# schematics.net
KiCad netlist of a schematic drawn in EasyEDA
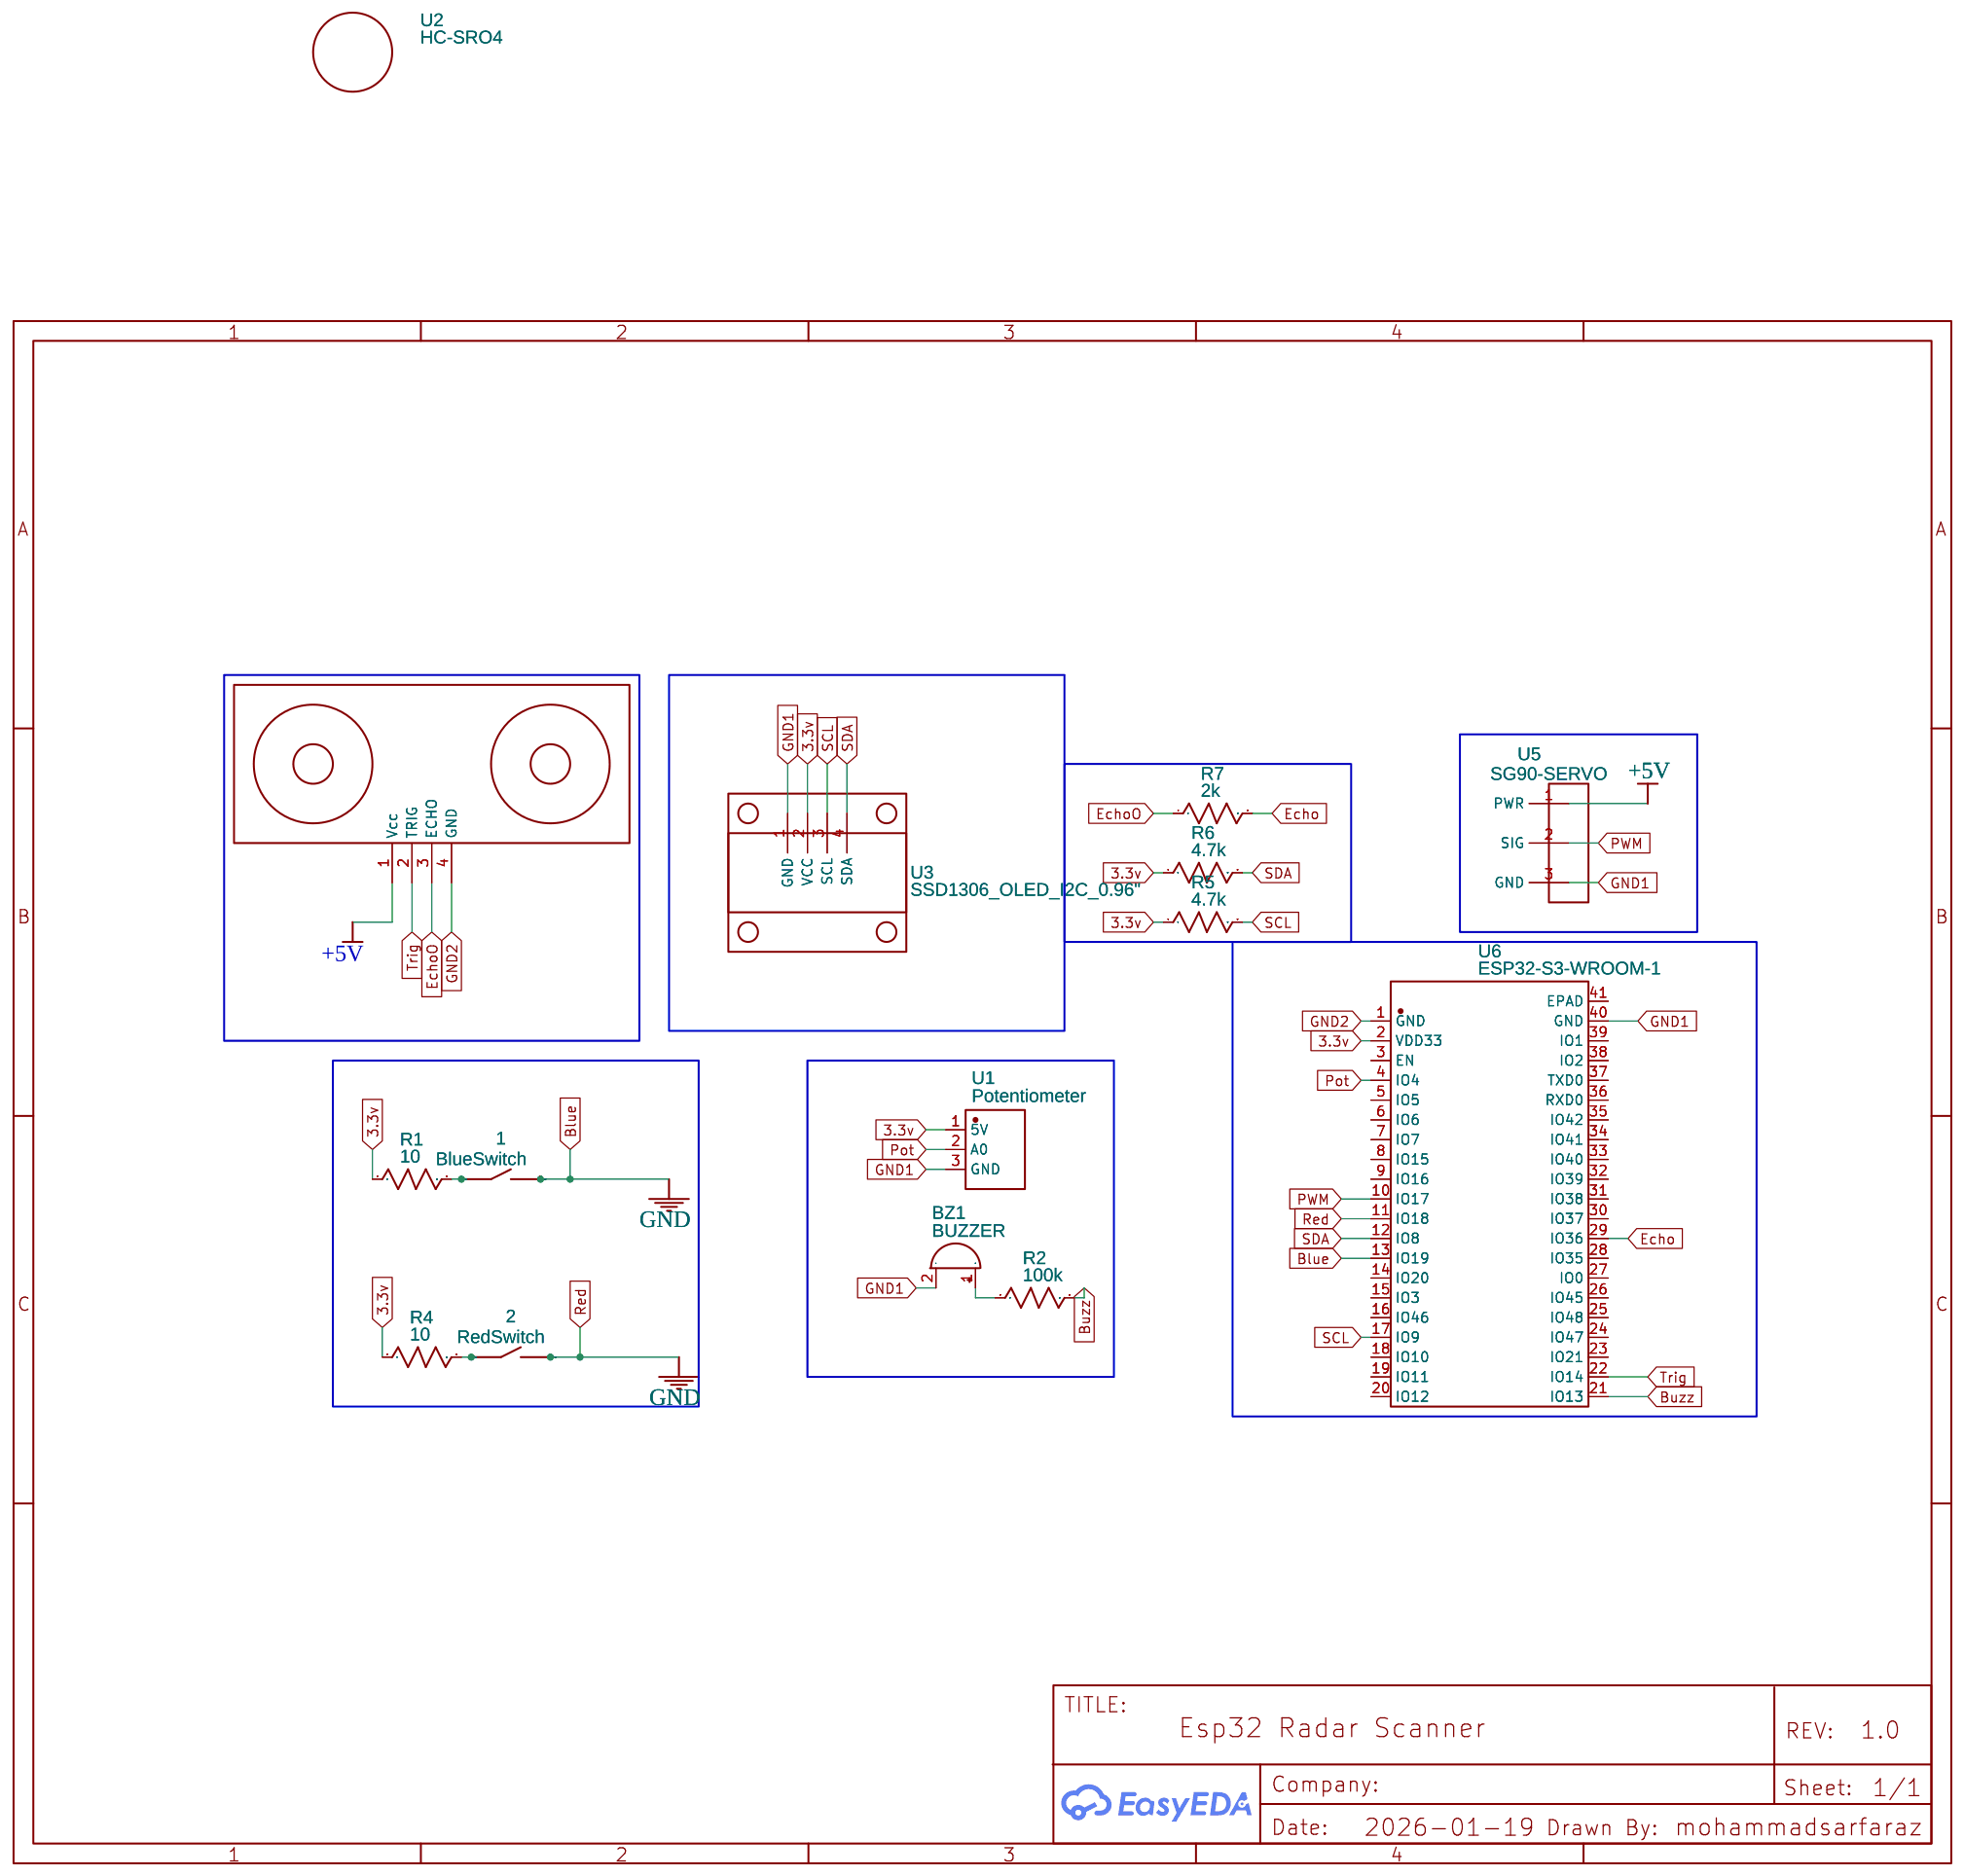
[diagram p0: schematic sheet]

(export (version "E")
  (design (tool "Eeschema 10.0.6"))
  (components
    (comp (ref "1") (value "BlueSwitch") (libsource (lib "") (part "4.5X4.5-SMD-TACTILE-SWITCH")))
    (comp (ref "2") (value "RedSwitch") (libsource (lib "") (part "4.5X4.5-SMD-TACTILE-SWITCH")))
    (comp (ref "BZ1") (value "BUZZER") (libsource (lib "") (part "BUZZER 12X9.5 FATHBOARD")))
    (comp (ref "R1") (value "10") (libsource (lib "") (part "R_0603_US")))
    (comp (ref "R2") (value "100k") (libsource (lib "") (part "R_0603_US")))
    (comp (ref "R4") (value "10") (libsource (lib "") (part "R_0603_US")))
    (comp (ref "R5") (value "4.7k") (libsource (lib "") (part "R_0603_US")))
    (comp (ref "R6") (value "4.7k") (libsource (lib "") (part "R_0603_US")))
    (comp (ref "R7") (value "2k") (libsource (lib "") (part "R_0603_US")))
    (comp (ref "U1") (value "Potentiometer") (libsource (lib "") (part "Potentiometer")))
    (comp (ref "U2") (value "HC-SRO4") (libsource (lib "") (part "HC-SRO4")))
    (comp (ref "U3")
      (value "SSD1306_OLED_I2C_0.96\"")
      (libsource (lib "") (part "SSD1306_OLED_I2C_0.96{dblquote}"))
    )
    (comp (ref "U5") (value "SG90-SERVO") (libsource (lib "") (part "SG90-SERVO")))
    (comp (ref "U6")
      (value "ESP32-S3-WROOM-1")
      (fields (field (name "Manufacturer") "Espressif Systems"))
      (libsource (lib "") (part "ESP32-S3-WROOM-1"))
    )
  )
  (nets
    (net (code "1") (name "+5V") (class "Default")
      (node (ref "U2") (pin "1") (pinfunction "Vcc_1") (pintype "unspecified"))
      (node (ref "U5") (pin "1") (pinfunction "PWR_1") (pintype "unspecified"))
    )
    (net (code "2") (name "3.3v") (class "Default")
      (node (ref "R1") (pin "1") (pinfunction "1_1") (pintype "unspecified"))
      (node (ref "R4") (pin "1") (pinfunction "1_1") (pintype "unspecified"))
      (node (ref "R5") (pin "1") (pinfunction "1_1") (pintype "unspecified"))
      (node (ref "R6") (pin "1") (pinfunction "1_1") (pintype "unspecified"))
      (node (ref "U1") (pin "1") (pinfunction "5V_1") (pintype "unspecified"))
      (node (ref "U3") (pin "2") (pinfunction "VCC_2") (pintype "unspecified"))
      (node (ref "U6") (pin "2") (pinfunction "VDD33_2") (pintype "unspecified"))
    )
    (net (code "3") (name "Blue") (class "Default")
      (node (ref "1") (pin "2.1") (pinfunction "S2_2.1") (pintype "bidirectional"))
      (node (ref "1") (pin "2.2") (pinfunction "S2_2.2") (pintype "bidirectional"))
      (node (ref "2") (pin "2.1") (pinfunction "S2_2.1") (pintype "bidirectional"))
      (node (ref "2") (pin "2.2") (pinfunction "S2_2.2") (pintype "bidirectional"))
      (node (ref "U6") (pin "11") (pinfunction "IO18_11") (pintype "unspecified"))
      (node (ref "U6") (pin "13") (pinfunction "IO19_13") (pintype "unspecified"))
    )
    (net (code "4") (name "Buzz") (class "Default")
      (node (ref "R2") (pin "2") (pinfunction "2_2") (pintype "unspecified"))
      (node (ref "U6") (pin "21") (pinfunction "IO13_21") (pintype "unspecified"))
    )
    (net (code "5") (name "Echo") (class "Default")
      (node (ref "R7") (pin "2") (pinfunction "2_2") (pintype "unspecified"))
      (node (ref "U6") (pin "29") (pinfunction "IO36_29") (pintype "unspecified"))
    )
    (net (code "6") (name "EchoO") (class "Default")
      (node (ref "R7") (pin "1") (pinfunction "1_1") (pintype "unspecified"))
      (node (ref "U2") (pin "3") (pinfunction "ECHO_3") (pintype "unspecified"))
    )
    (net (code "7") (name "GND1") (class "Default")
      (node (ref "BZ1") (pin "2") (pinfunction "-_2") (pintype "unspecified"))
      (node (ref "U1") (pin "3") (pinfunction "GND_3") (pintype "unspecified"))
      (node (ref "U3") (pin "1") (pinfunction "GND_1") (pintype "unspecified"))
      (node (ref "U5") (pin "3") (pinfunction "GND_3") (pintype "unspecified"))
      (node (ref "U6") (pin "40") (pinfunction "GND_40") (pintype "unspecified"))
    )
    (net (code "8") (name "GND2") (class "Default")
      (node (ref "U2") (pin "4") (pinfunction "GND_4") (pintype "unspecified"))
      (node (ref "U6") (pin "1") (pinfunction "GND_1") (pintype "unspecified"))
    )
    (net (code "9") (name "Net-(1-S1-Pad1.1)") (class "Default")
      (node (ref "1") (pin "1.1") (pinfunction "S1_1.1") (pintype "bidirectional"))
      (node (ref "1") (pin "1.2") (pinfunction "S1_1.2") (pintype "bidirectional"))
      (node (ref "R1") (pin "2") (pinfunction "2_2") (pintype "unspecified"))
    )
    (net (code "10") (name "Net-(2-S1-Pad1.1)") (class "Default")
      (node (ref "2") (pin "1.1") (pinfunction "S1_1.1") (pintype "bidirectional"))
      (node (ref "2") (pin "1.2") (pinfunction "S1_1.2") (pintype "bidirectional"))
      (node (ref "R4") (pin "2") (pinfunction "2_2") (pintype "unspecified"))
    )
    (net (code "11") (name "Net-(BZ1-+)") (class "Default")
      (node (ref "BZ1") (pin "1") (pinfunction "+_1") (pintype "unspecified"))
      (node (ref "R2") (pin "1") (pinfunction "1_1") (pintype "unspecified"))
    )
    (net (code "12") (name "PWM") (class "Default")
      (node (ref "U5") (pin "2") (pinfunction "SIG_2") (pintype "unspecified"))
      (node (ref "U6") (pin "10") (pinfunction "IO17_10") (pintype "unspecified"))
    )
    (net (code "13") (name "Pot") (class "Default")
      (node (ref "U1") (pin "2") (pinfunction "A0_2") (pintype "unspecified"))
      (node (ref "U6") (pin "4") (pinfunction "IO4_4") (pintype "unspecified"))
    )
    (net (code "14") (name "SCL") (class "Default")
      (node (ref "R5") (pin "2") (pinfunction "2_2") (pintype "unspecified"))
      (node (ref "U3") (pin "3") (pinfunction "SCL_3") (pintype "unspecified"))
      (node (ref "U6") (pin "17") (pinfunction "IO9_17") (pintype "unspecified"))
    )
    (net (code "15") (name "SDA") (class "Default")
      (node (ref "R6") (pin "2") (pinfunction "2_2") (pintype "unspecified"))
      (node (ref "U3") (pin "4") (pinfunction "SDA_4") (pintype "unspecified"))
      (node (ref "U6") (pin "12") (pinfunction "IO8_12") (pintype "unspecified"))
    )
    (net (code "16") (name "Trig") (class "Default")
      (node (ref "U2") (pin "2") (pinfunction "TRIG_2") (pintype "unspecified"))
      (node (ref "U6") (pin "22") (pinfunction "IO14_22") (pintype "unspecified"))
    )
    (net (code "17") (name "unconnected-(U6-EN-Pad3)") (class "Default")
      (node (ref "U6") (pin "3") (pinfunction "EN_3") (pintype "unspecified"))
    )
    (net (code "18") (name "unconnected-(U6-EPAD-Pad41)") (class "Default")
      (node (ref "U6") (pin "41") (pinfunction "EPAD_41") (pintype "unspecified"))
    )
    (net (code "19") (name "unconnected-(U6-IO0-Pad27)") (class "Default")
      (node (ref "U6") (pin "27") (pinfunction "IO0_27") (pintype "unspecified"))
    )
    (net (code "20") (name "unconnected-(U6-IO1-Pad39)") (class "Default")
      (node (ref "U6") (pin "39") (pinfunction "IO1_39") (pintype "unspecified"))
    )
    (net (code "21") (name "unconnected-(U6-IO2-Pad38)") (class "Default")
      (node (ref "U6") (pin "38") (pinfunction "IO2_38") (pintype "unspecified"))
    )
    (net (code "22") (name "unconnected-(U6-IO3-Pad15)") (class "Default")
      (node (ref "U6") (pin "15") (pinfunction "IO3_15") (pintype "unspecified"))
    )
    (net (code "23") (name "unconnected-(U6-IO5-Pad5)") (class "Default")
      (node (ref "U6") (pin "5") (pinfunction "IO5_5") (pintype "unspecified"))
    )
    (net (code "24") (name "unconnected-(U6-IO6-Pad6)") (class "Default")
      (node (ref "U6") (pin "6") (pinfunction "IO6_6") (pintype "unspecified"))
    )
    (net (code "25") (name "unconnected-(U6-IO7-Pad7)") (class "Default")
      (node (ref "U6") (pin "7") (pinfunction "IO7_7") (pintype "unspecified"))
    )
    (net (code "26") (name "unconnected-(U6-IO10-Pad18)") (class "Default")
      (node (ref "U6") (pin "18") (pinfunction "IO10_18") (pintype "unspecified"))
    )
    (net (code "27") (name "unconnected-(U6-IO11-Pad19)") (class "Default")
      (node (ref "U6") (pin "19") (pinfunction "IO11_19") (pintype "unspecified"))
    )
    (net (code "28") (name "unconnected-(U6-IO12-Pad20)") (class "Default")
      (node (ref "U6") (pin "20") (pinfunction "IO12_20") (pintype "unspecified"))
    )
    (net (code "29") (name "unconnected-(U6-IO15-Pad8)") (class "Default")
      (node (ref "U6") (pin "8") (pinfunction "IO15_8") (pintype "unspecified"))
    )
    (net (code "30") (name "unconnected-(U6-IO16-Pad9)") (class "Default")
      (node (ref "U6") (pin "9") (pinfunction "IO16_9") (pintype "unspecified"))
    )
    (net (code "31") (name "unconnected-(U6-IO20-Pad14)") (class "Default")
      (node (ref "U6") (pin "14") (pinfunction "IO20_14") (pintype "unspecified"))
    )
    (net (code "32") (name "unconnected-(U6-IO21-Pad23)") (class "Default")
      (node (ref "U6") (pin "23") (pinfunction "IO21_23") (pintype "unspecified"))
    )
    (net (code "33") (name "unconnected-(U6-IO35-Pad28)") (class "Default")
      (node (ref "U6") (pin "28") (pinfunction "IO35_28") (pintype "unspecified"))
    )
    (net (code "34") (name "unconnected-(U6-IO37-Pad30)") (class "Default")
      (node (ref "U6") (pin "30") (pinfunction "IO37_30") (pintype "unspecified"))
    )
    (net (code "35") (name "unconnected-(U6-IO38-Pad31)") (class "Default")
      (node (ref "U6") (pin "31") (pinfunction "IO38_31") (pintype "unspecified"))
    )
    (net (code "36") (name "unconnected-(U6-IO39-Pad32)") (class "Default")
      (node (ref "U6") (pin "32") (pinfunction "IO39_32") (pintype "unspecified"))
    )
    (net (code "37") (name "unconnected-(U6-IO40-Pad33)") (class "Default")
      (node (ref "U6") (pin "33") (pinfunction "IO40_33") (pintype "unspecified"))
    )
    (net (code "38") (name "unconnected-(U6-IO41-Pad34)") (class "Default")
      (node (ref "U6") (pin "34") (pinfunction "IO41_34") (pintype "unspecified"))
    )
    (net (code "39") (name "unconnected-(U6-IO42-Pad35)") (class "Default")
      (node (ref "U6") (pin "35") (pinfunction "IO42_35") (pintype "unspecified"))
    )
    (net (code "40") (name "unconnected-(U6-IO45-Pad26)") (class "Default")
      (node (ref "U6") (pin "26") (pinfunction "IO45_26") (pintype "unspecified"))
    )
    (net (code "41") (name "unconnected-(U6-IO46-Pad16)") (class "Default")
      (node (ref "U6") (pin "16") (pinfunction "IO46_16") (pintype "unspecified"))
    )
    (net (code "42") (name "unconnected-(U6-IO47-Pad24)") (class "Default")
      (node (ref "U6") (pin "24") (pinfunction "IO47_24") (pintype "unspecified"))
    )
    (net (code "43") (name "unconnected-(U6-IO48-Pad25)") (class "Default")
      (node (ref "U6") (pin "25") (pinfunction "IO48_25") (pintype "unspecified"))
    )
    (net (code "44") (name "unconnected-(U6-RXD0-Pad36)") (class "Default")
      (node (ref "U6") (pin "36") (pinfunction "RXD0_36") (pintype "unspecified"))
    )
    (net (code "45") (name "unconnected-(U6-TXD0-Pad37)") (class "Default")
      (node (ref "U6") (pin "37") (pinfunction "TXD0_37") (pintype "unspecified"))
    )
  )
)
